# TopLevel.net
KiCad netlist of a schematic drawn in Altium Designer
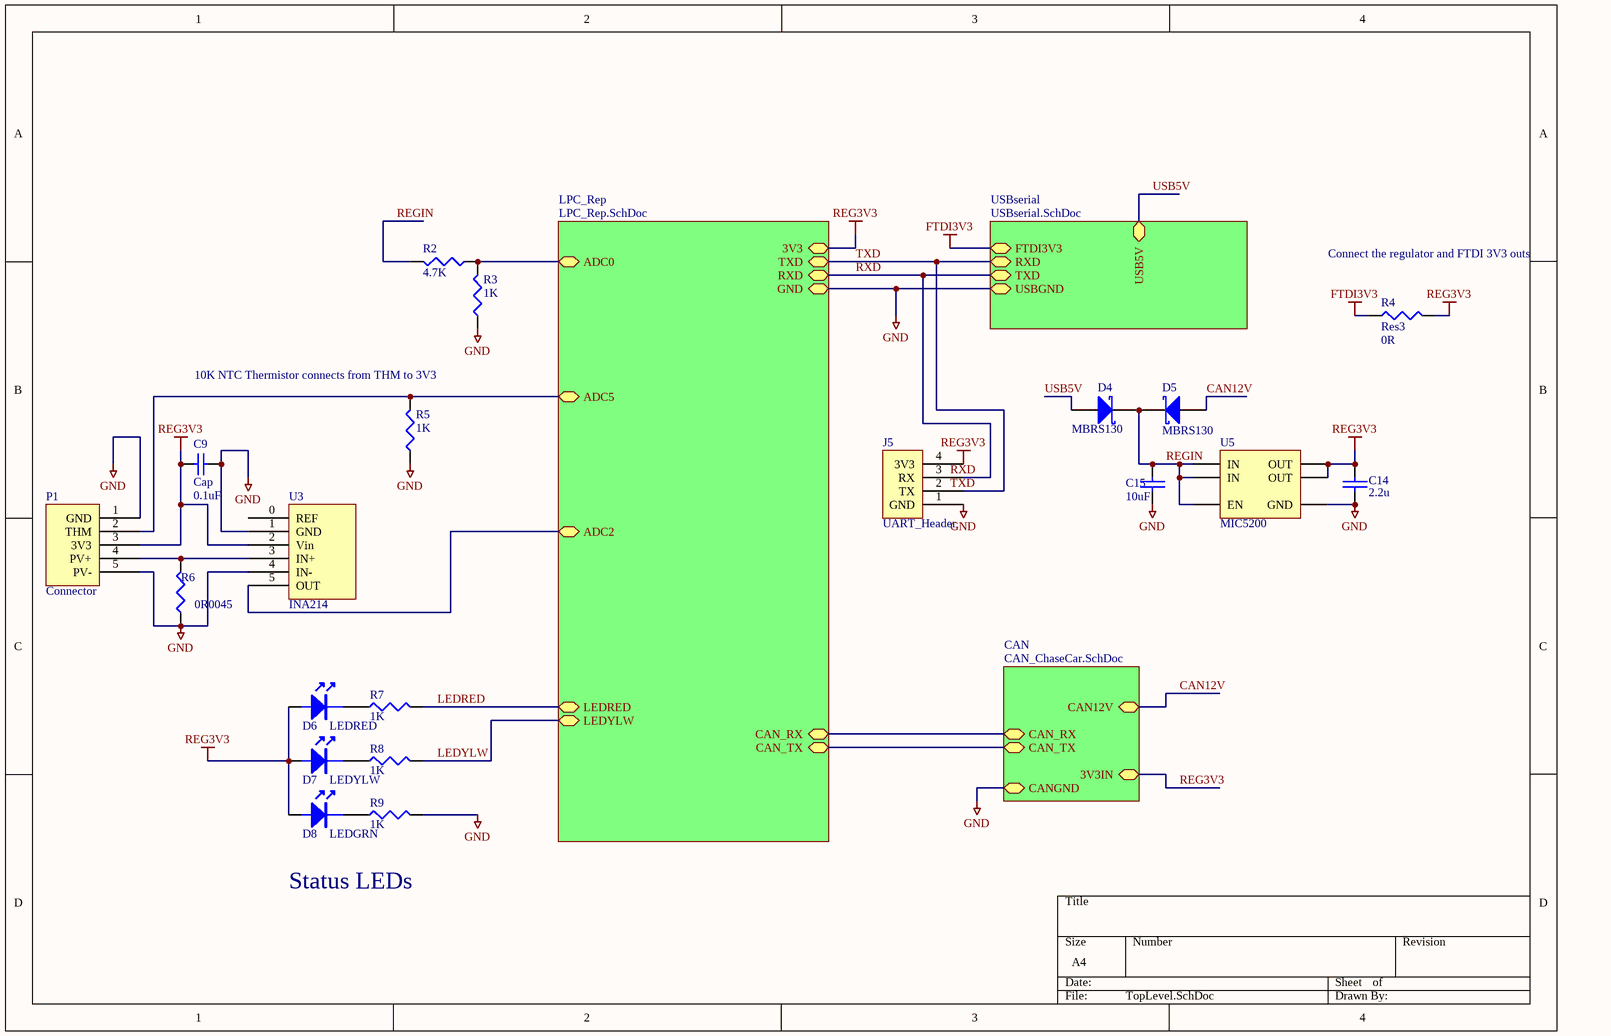
[diagram p0: TopLevel.SchDoc]

(export (version "E")
  (design (tool "Eeschema 10.0.6"))
  (components
    (comp (ref "C9")
      (value "Cap")
      (footprint "0603")
      (description "Capacitor")
      (fields (field (name "ALTIUM_VALUE") "0.1uF") (field (name "PUBLISHER") "Altium Limited"))
      (libsource (lib "Miscellaneous Devices") (part "Cap"))
    )
    (comp (ref "C14")
      (value "2.2u")
      (footprint "0603")
      (description "Capacitor")
      (libsource (lib "*") (part "CAP"))
    )
    (comp (ref "C15")
      (value "10uF")
      (footprint "0805")
      (description "Capacitor")
      (fields (field (name "Comment") "10u"))
      (libsource (lib "*") (part "CAP"))
    )
    (comp (ref "D4")
      (value "MBRS130")
      (footprint "SMB")
      (description "Schottky Diode")
      (libsource (lib "RCLDQ") (part "D SCHOTTKY"))
    )
    (comp (ref "D5")
      (value "MBRS130")
      (footprint "SMB")
      (description "Schottky Diode")
      (libsource (lib "RCLDQ") (part "D SCHOTTKY"))
    )
    (comp (ref "D6") (value "LEDRED") (footprint "0805LED") (libsource (lib "RCLDQ") (part "LED")))
    (comp (ref "D7") (value "LEDYLW") (footprint "0805LED") (libsource (lib "RCLDQ") (part "LED")))
    (comp (ref "D8") (value "LEDGRN") (footprint "0805LED") (libsource (lib "RCLDQ") (part "LED")))
    (comp (ref "J5")
      (value "UART_Header")
      (footprint "TiltLib:IDC4")
      (libsource (lib "2009_BatteryMaster") (part "UART_Header"))
    )
    (comp (ref "P1") (value "Connector") (footprint "TermBlock5") (libsource (lib "SunRef") (part "CONN")))
    (comp (ref "R2")
      (value "4.7K")
      (footprint "0603")
      (description "Resistor")
      (libsource (lib "RCLDQ") (part "RES1"))
    )
    (comp (ref "R3")
      (value "1K")
      (footprint "0603")
      (description "Resistor")
      (libsource (lib "RCLDQ") (part "RES1"))
    )
    (comp (ref "R4")
      (value "Res3")
      (footprint "0603")
      (description "Resistor")
      (fields (field (name "ALTIUM_VALUE") "0R") (field (name "PUBLISHER") "Altium Limited"))
      (libsource (lib "Miscellaneous Devices") (part "Res3"))
    )
    (comp (ref "R5")
      (value "1K")
      (footprint "0603")
      (description "Resistor")
      (libsource (lib "RCLDQ") (part "RES1"))
    )
    (comp (ref "R6")
      (value "0R0045")
      (footprint "1206")
      (description "Resistor")
      (libsource (lib "RCLDQ") (part "RES1"))
    )
    (comp (ref "R7")
      (value "1K")
      (footprint "0603")
      (description "Resistor")
      (libsource (lib "RCLDQ") (part "RES1"))
    )
    (comp (ref "R8")
      (value "1K")
      (footprint "0603")
      (description "Resistor")
      (libsource (lib "RCLDQ") (part "RES1"))
    )
    (comp (ref "R9")
      (value "1K")
      (footprint "0603")
      (description "Resistor")
      (libsource (lib "RCLDQ") (part "RES1"))
    )
    (comp (ref "U3") (value "INA214") (footprint "SOP6 - INA214") (libsource (lib "SunRef") (part "INA214")))
    (comp (ref "U5")
      (value "MIC5200")
      (footprint "SO8")
      (description "MIC5200 - SO8")
      (libsource (lib "*") (part "MIC5200"))
    )
  )
  (nets
    (net (code "1") (name "/ADC0") (class "Default")
      (node (ref "R2") (pin "1") (pinfunction "1_1") (pintype "passive"))
      (node (ref "R3") (pin "2") (pinfunction "2_2") (pintype "passive"))
    )
    (net (code "2") (name "/ADC2") (class "Default")
      (node (ref "U3") (pin "5") (pinfunction "OUT_5") (pintype "passive"))
    )
    (net (code "3") (name "/ADC5") (class "Default")
      (node (ref "P1") (pin "2") (pinfunction "THM_2") (pintype "passive"))
      (node (ref "R5") (pin "2") (pinfunction "2_2") (pintype "passive"))
    )
    (net (code "4") (name "/CAN12V") (class "Default")
      (node (ref "D5") (pin "A") (pinfunction "A_A") (pintype "passive"))
    )
    (net (code "7") (name "/LEDRED") (class "Default")
      (node (ref "R7") (pin "2") (pinfunction "2_2") (pintype "passive"))
    )
    (net (code "8") (name "/LEDYLW") (class "Default")
      (node (ref "R8") (pin "2") (pinfunction "2_2") (pintype "passive"))
    )
    (net (code "9") (name "/REGIN") (class "Default")
      (node (ref "C15") (pin "1") (pinfunction "1_1") (pintype "passive"))
      (node (ref "D4") (pin "K") (pinfunction "K_K") (pintype "passive"))
      (node (ref "D5") (pin "K") (pinfunction "K_K") (pintype "passive"))
      (node (ref "R2") (pin "2") (pinfunction "2_2") (pintype "passive"))
      (node (ref "U5") (pin "5") (pinfunction "EN_5") (pintype "passive"))
      (node (ref "U5") (pin "7") (pinfunction "IN_7") (pintype "passive"))
      (node (ref "U5") (pin "8") (pinfunction "IN_8") (pintype "passive"))
    )
    (net (code "10") (name "/RXD") (class "Default")
      (node (ref "J5") (pin "3") (pinfunction "RX_3") (pintype "passive"))
    )
    (net (code "11") (name "/TXD") (class "Default")
      (node (ref "J5") (pin "2") (pinfunction "TX_2") (pintype "passive"))
    )
    (net (code "12") (name "/USB5V") (class "Default")
      (node (ref "D4") (pin "A") (pinfunction "A_A") (pintype "passive"))
    )
    (net (code "13") (name "FTDI3V3") (class "Default")
      (node (ref "R4") (pin "1") (pinfunction "1_1") (pintype "passive"))
    )
    (net (code "14") (name "GND") (class "Default")
      (node (ref "C14") (pin "1") (pinfunction "1_1") (pintype "passive"))
      (node (ref "C15") (pin "2") (pinfunction "2_2") (pintype "passive"))
      (node (ref "C9") (pin "2") (pinfunction "2_2") (pintype "passive"))
      (node (ref "J5") (pin "1") (pinfunction "GND_1") (pintype "passive"))
      (node (ref "P1") (pin "1") (pinfunction "GND_1") (pintype "passive"))
      (node (ref "P1") (pin "5") (pinfunction "PV-_5") (pintype "passive"))
      (node (ref "R3") (pin "1") (pinfunction "1_1") (pintype "passive"))
      (node (ref "R5") (pin "1") (pinfunction "1_1") (pintype "passive"))
      (node (ref "R6") (pin "1") (pinfunction "1_1") (pintype "passive"))
      (node (ref "R9") (pin "2") (pinfunction "2_2") (pintype "passive"))
      (node (ref "U3") (pin "1") (pinfunction "GND_1") (pintype "passive"))
      (node (ref "U3") (pin "4") (pinfunction "IN-_4") (pintype "passive"))
      (node (ref "U5") (pin "4") (pinfunction "GND_4") (pintype "passive"))
    )
    (net (code "15") (name "Net-(D6-PadK)") (class "Default")
      (node (ref "D6") (pin "K") (pinfunction "K_K") (pintype "passive"))
      (node (ref "R7") (pin "1") (pinfunction "1_1") (pintype "passive"))
    )
    (net (code "16") (name "Net-(D7-PadK)") (class "Default")
      (node (ref "D7") (pin "K") (pinfunction "K_K") (pintype "passive"))
      (node (ref "R8") (pin "1") (pinfunction "1_1") (pintype "passive"))
    )
    (net (code "17") (name "Net-(D8-PadK)") (class "Default")
      (node (ref "D8") (pin "K") (pinfunction "K_K") (pintype "passive"))
      (node (ref "R9") (pin "1") (pinfunction "1_1") (pintype "passive"))
    )
    (net (code "18") (name "Net-(P1-PV+)") (class "Default")
      (node (ref "P1") (pin "4") (pinfunction "PV+_4") (pintype "passive"))
      (node (ref "R6") (pin "2") (pinfunction "2_2") (pintype "passive"))
      (node (ref "U3") (pin "3") (pinfunction "IN+_3") (pintype "passive"))
    )
    (net (code "19") (name "REG3V3") (class "Default")
      (node (ref "C14") (pin "2") (pinfunction "2_2") (pintype "passive"))
      (node (ref "C9") (pin "1") (pinfunction "1_1") (pintype "passive"))
      (node (ref "D6") (pin "A") (pinfunction "A_A") (pintype "passive"))
      (node (ref "D7") (pin "A") (pinfunction "A_A") (pintype "passive"))
      (node (ref "D8") (pin "A") (pinfunction "A_A") (pintype "passive"))
      (node (ref "J5") (pin "4") (pinfunction "3V3_4") (pintype "passive"))
      (node (ref "P1") (pin "3") (pinfunction "3V3_3") (pintype "passive"))
      (node (ref "R4") (pin "2") (pinfunction "2_2") (pintype "passive"))
      (node (ref "U3") (pin "2") (pinfunction "Vin_2") (pintype "passive"))
      (node (ref "U5") (pin "1") (pinfunction "OUT_1") (pintype "passive"))
      (node (ref "U5") (pin "2") (pinfunction "OUT_2") (pintype "passive"))
    )
    (net (code "20") (name "unconnected-(U3-REF-Pad0)") (class "Default")
      (node (ref "U3") (pin "0") (pinfunction "REF_0") (pintype "passive"))
    )
  )
)
